# Un_Battery_V2_1.net
KiCad netlist of a schematic drawn in EAGLE
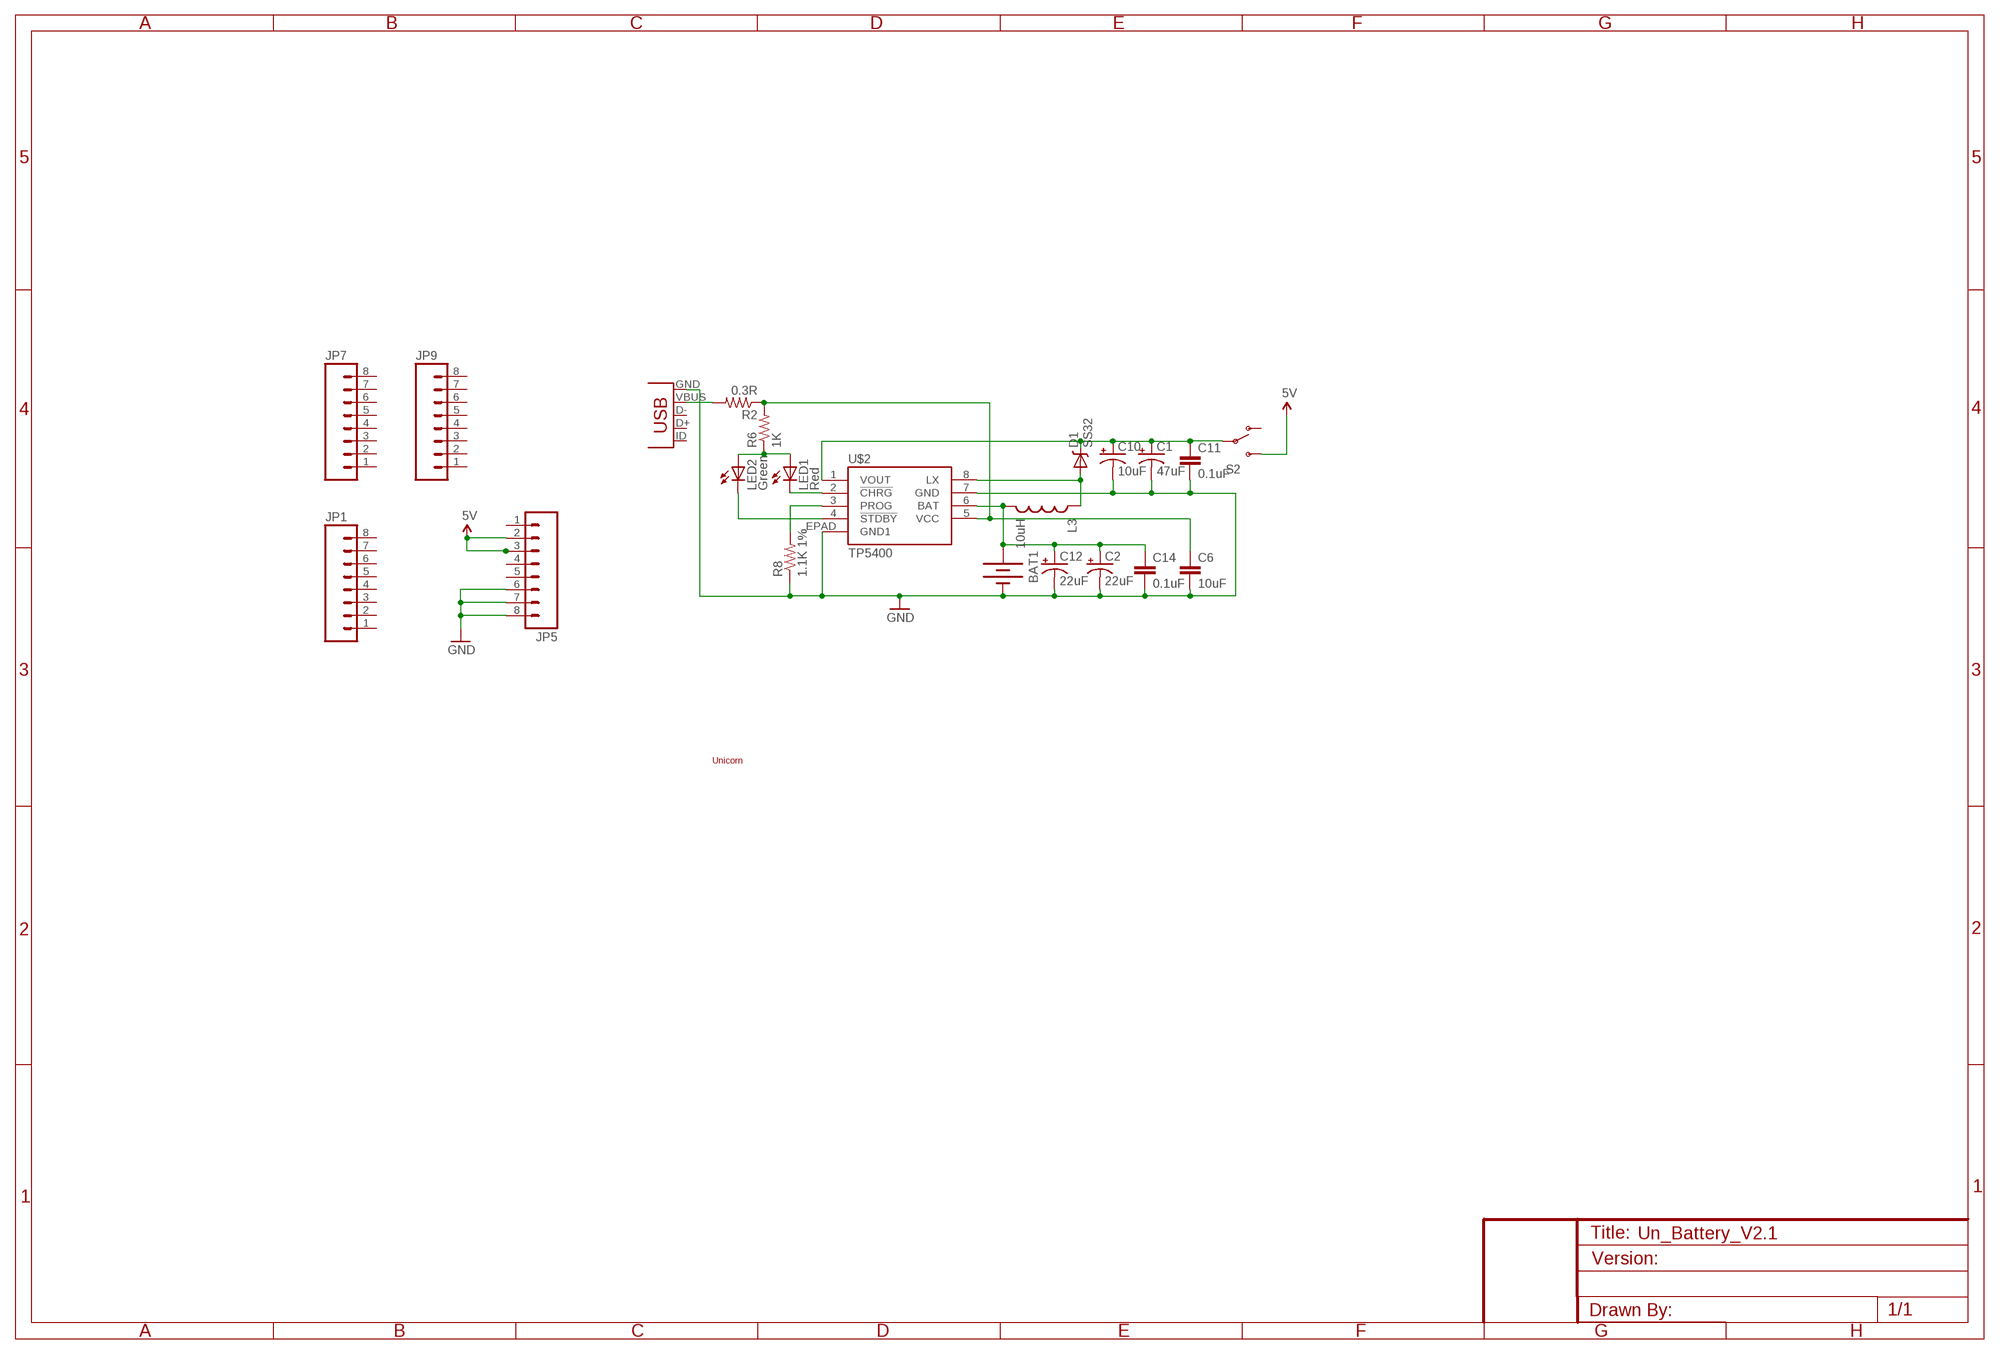
[diagram p0: schematic, sheet 1]

(export (version "E")
  (design (tool "Eeschema 10.0.6"))
  (components
    (comp (ref "BAT1")
      (value "BATTERYLIPO2")
      (footprint "eagle-import:BATTERY-LIPO2")
      (libsource (lib "eagle-import") (part "BATTERYLIPO2"))
    )
    (comp (ref "C1")
      (value "47uF")
      (footprint "eagle-import:EIA3216")
      (libsource (lib "eagle-import") (part "CAP_POL1206"))
    )
    (comp (ref "C2")
      (value "22uF")
      (footprint "eagle-import:EIA3216")
      (libsource (lib "eagle-import") (part "CAP_POL1206"))
    )
    (comp (ref "C6")
      (value "10uF")
      (footprint "eagle-import:1206")
      (libsource (lib "eagle-import") (part "CAP1206"))
    )
    (comp (ref "C10")
      (value "10uF")
      (footprint "eagle-import:EIA3216")
      (libsource (lib "eagle-import") (part "CAP_POL1206"))
    )
    (comp (ref "C11")
      (value "0.1uF")
      (footprint "eagle-import:0603-CAP")
      (libsource (lib "eagle-import") (part "CAP0603-CAP"))
    )
    (comp (ref "C12")
      (value "22uF")
      (footprint "eagle-import:EIA3216")
      (libsource (lib "eagle-import") (part "CAP_POL1206"))
    )
    (comp (ref "C14")
      (value "0.1uF")
      (footprint "eagle-import:0603-CAP")
      (libsource (lib "eagle-import") (part "CAP0603-CAP"))
    )
    (comp (ref "D1")
      (value "SS32")
      (footprint "eagle-import:SMA-DIODE")
      (libsource (lib "eagle-import") (part "DIODE-SCHOTTKY_"))
    )
    (comp (ref "JP1")
      (value "M081X08")
      (footprint "eagle-import:1X08")
      (libsource (lib "eagle-import") (part "M081X08"))
    )
    (comp (ref "JP5")
      (value "M081X08")
      (footprint "eagle-import:1X08")
      (libsource (lib "eagle-import") (part "M081X08"))
    )
    (comp (ref "JP7")
      (value "M081X08")
      (footprint "eagle-import:1X08")
      (libsource (lib "eagle-import") (part "M081X08"))
    )
    (comp (ref "JP9")
      (value "M081X08")
      (footprint "eagle-import:1X08")
      (libsource (lib "eagle-import") (part "M081X08"))
    )
    (comp (ref "L3")
      (value "10uH")
      (footprint "eagle-import:CR32")
      (libsource (lib "eagle-import") (part "INDUCTOR_CR32"))
    )
    (comp (ref "LED1")
      (value "Red")
      (footprint "eagle-import:LED-0603")
      (libsource (lib "eagle-import") (part "LED0603"))
    )
    (comp (ref "LED2")
      (value "Green")
      (footprint "eagle-import:LED-0603")
      (libsource (lib "eagle-import") (part "LED0603"))
    )
    (comp (ref "R2")
      (value "0.3R")
      (footprint "eagle-import:1206")
      (libsource (lib "eagle-import") (part "RESISTOR1206"))
    )
    (comp (ref "R6")
      (value "1K")
      (footprint "eagle-import:0603-RES")
      (libsource (lib "eagle-import") (part "RESISTOR0603-RES"))
    )
    (comp (ref "R8")
      (value "1.1K 1%")
      (footprint "eagle-import:0603-RES")
      (libsource (lib "eagle-import") (part "RESISTOR0603-RES"))
    )
    (comp (ref "S2")
      (value "SWITCH-SPST")
      (footprint "eagle-import:SWITCH-SPDT2")
      (libsource (lib "eagle-import") (part "SWITCH-SPST"))
    )
    (comp (ref "U$2")
      (value "TP5400")
      (footprint "eagle-import:SO08-EPAD")
      (libsource (lib "eagle-import") (part "TP5400"))
    )
    (comp (ref "U$6")
      (value "USB_5-SMD")
      (footprint "eagle-import:USB-MINIB")
      (libsource (lib "eagle-import") (part "USB_5-SMD"))
    )
    (comp (ref "U$7")
      (value "UNICORN_1")
      (footprint "eagle-import:UNICORN_1")
      (libsource (lib "eagle-import") (part "UNICORN_1"))
    )
  )
  (nets
    (net (code "1") (name "5V") (class "Default")
      (node (ref "JP5") (pin "2") (pinfunction "2_2") (pintype "passive"))
      (node (ref "JP5") (pin "3") (pinfunction "3_3") (pintype "passive"))
      (node (ref "S2") (pin "3") (pinfunction "S_3") (pintype "passive"))
    )
    (net (code "2") (name "GND") (class "Default")
      (node (ref "BAT1") (pin "-") (pinfunction "-_-") (pintype "power_in"))
      (node (ref "C1") (pin "C") (pinfunction "-_C") (pintype "passive"))
      (node (ref "C10") (pin "C") (pinfunction "-_C") (pintype "passive"))
      (node (ref "C11") (pin "2") (pinfunction "2_2") (pintype "passive"))
      (node (ref "C12") (pin "C") (pinfunction "-_C") (pintype "passive"))
      (node (ref "C14") (pin "2") (pinfunction "2_2") (pintype "passive"))
      (node (ref "C2") (pin "C") (pinfunction "-_C") (pintype "passive"))
      (node (ref "C6") (pin "2") (pinfunction "2_2") (pintype "passive"))
      (node (ref "JP5") (pin "6") (pinfunction "6_6") (pintype "passive"))
      (node (ref "JP5") (pin "7") (pinfunction "7_7") (pintype "passive"))
      (node (ref "JP5") (pin "8") (pinfunction "8_8") (pintype "passive"))
      (node (ref "R8") (pin "1") (pinfunction "1_1") (pintype "passive"))
      (node (ref "U$2") (pin "7") (pinfunction "GND_7") (pintype "bidirectional"))
      (node (ref "U$2") (pin "EPAD") (pinfunction "GND1_EPAD") (pintype "power_in"))
      (node (ref "U$6") (pin "GND") (pinfunction "GND_GND") (pintype "bidirectional"))
    )
    (net (code "3") (name "Net-(C1-+)") (class "Default")
      (node (ref "C1") (pin "A") (pinfunction "+_A") (pintype "passive"))
      (node (ref "C10") (pin "A") (pinfunction "+_A") (pintype "passive"))
      (node (ref "C11") (pin "1") (pinfunction "1_1") (pintype "passive"))
      (node (ref "D1") (pin "C") (pinfunction "C_C") (pintype "passive"))
      (node (ref "S2") (pin "2") (pinfunction "P_2") (pintype "passive"))
      (node (ref "U$2") (pin "1") (pinfunction "VOUT_1") (pintype "bidirectional"))
    )
    (net (code "4") (name "Net-(C12-+)") (class "Default")
      (node (ref "BAT1") (pin "+") (pinfunction "+_+") (pintype "power_in"))
      (node (ref "C12") (pin "A") (pinfunction "+_A") (pintype "passive"))
      (node (ref "C14") (pin "1") (pinfunction "1_1") (pintype "passive"))
      (node (ref "C2") (pin "A") (pinfunction "+_A") (pintype "passive"))
      (node (ref "L3") (pin "P$2") (pinfunction "2_P$2") (pintype "passive"))
      (node (ref "U$2") (pin "6") (pinfunction "BAT_6") (pintype "bidirectional"))
    )
    (net (code "5") (name "Net-(L3-1)") (class "Default")
      (node (ref "D1") (pin "A") (pinfunction "A_A") (pintype "passive"))
      (node (ref "L3") (pin "P$1") (pinfunction "1_P$1") (pintype "passive"))
      (node (ref "U$2") (pin "8") (pinfunction "LX_8") (pintype "power_in"))
    )
    (net (code "6") (name "Net-(LED1-PadA)") (class "Default")
      (node (ref "LED1") (pin "A") (pinfunction "A_A") (pintype "passive"))
      (node (ref "LED2") (pin "A") (pinfunction "A_A") (pintype "passive"))
      (node (ref "R6") (pin "1") (pinfunction "1_1") (pintype "passive"))
    )
    (net (code "7") (name "Net-(R2-Pad2)") (class "Default")
      (node (ref "R2") (pin "2") (pinfunction "2_2") (pintype "passive"))
      (node (ref "U$6") (pin "VBUS") (pinfunction "VBUS_VBUS") (pintype "bidirectional"))
    )
    (net (code "8") (name "Net-(U$2-PROG)") (class "Default")
      (node (ref "R8") (pin "2") (pinfunction "2_2") (pintype "passive"))
      (node (ref "U$2") (pin "3") (pinfunction "PROG_3") (pintype "bidirectional"))
    )
    (net (code "9") (name "Net-(U$2-VCC)") (class "Default")
      (node (ref "C6") (pin "1") (pinfunction "1_1") (pintype "passive"))
      (node (ref "R2") (pin "1") (pinfunction "1_1") (pintype "passive"))
      (node (ref "R6") (pin "2") (pinfunction "2_2") (pintype "passive"))
      (node (ref "U$2") (pin "5") (pinfunction "VCC_5") (pintype "bidirectional"))
    )
    (net (code "10") (name "Net-(U$2-~{CHRG})") (class "Default")
      (node (ref "LED1") (pin "C") (pinfunction "C_C") (pintype "passive"))
      (node (ref "U$2") (pin "2") (pinfunction "~{CHRG}_2") (pintype "bidirectional"))
    )
    (net (code "11") (name "Net-(U$2-~{STDBY})") (class "Default")
      (node (ref "LED2") (pin "C") (pinfunction "C_C") (pintype "passive"))
      (node (ref "U$2") (pin "4") (pinfunction "~{STDBY}_4") (pintype "power_in"))
    )
    (net (code "12") (name "unconnected-(JP1-Pad1)") (class "Default")
      (node (ref "JP1") (pin "1") (pinfunction "1_1") (pintype "passive"))
    )
    (net (code "13") (name "unconnected-(JP1-Pad2)") (class "Default")
      (node (ref "JP1") (pin "2") (pinfunction "2_2") (pintype "passive"))
    )
    (net (code "14") (name "unconnected-(JP1-Pad3)") (class "Default")
      (node (ref "JP1") (pin "3") (pinfunction "3_3") (pintype "passive"))
    )
    (net (code "15") (name "unconnected-(JP1-Pad4)") (class "Default")
      (node (ref "JP1") (pin "4") (pinfunction "4_4") (pintype "passive"))
    )
    (net (code "16") (name "unconnected-(JP1-Pad5)") (class "Default")
      (node (ref "JP1") (pin "5") (pinfunction "5_5") (pintype "passive"))
    )
    (net (code "17") (name "unconnected-(JP1-Pad6)") (class "Default")
      (node (ref "JP1") (pin "6") (pinfunction "6_6") (pintype "passive"))
    )
    (net (code "18") (name "unconnected-(JP1-Pad7)") (class "Default")
      (node (ref "JP1") (pin "7") (pinfunction "7_7") (pintype "passive"))
    )
    (net (code "19") (name "unconnected-(JP1-Pad8)") (class "Default")
      (node (ref "JP1") (pin "8") (pinfunction "8_8") (pintype "passive"))
    )
    (net (code "20") (name "unconnected-(JP5-Pad1)") (class "Default")
      (node (ref "JP5") (pin "1") (pinfunction "1_1") (pintype "passive"))
    )
    (net (code "21") (name "unconnected-(JP5-Pad4)") (class "Default")
      (node (ref "JP5") (pin "4") (pinfunction "4_4") (pintype "passive"))
    )
    (net (code "22") (name "unconnected-(JP5-Pad5)") (class "Default")
      (node (ref "JP5") (pin "5") (pinfunction "5_5") (pintype "passive"))
    )
    (net (code "23") (name "unconnected-(JP7-Pad1)") (class "Default")
      (node (ref "JP7") (pin "1") (pinfunction "1_1") (pintype "passive"))
    )
    (net (code "24") (name "unconnected-(JP7-Pad2)") (class "Default")
      (node (ref "JP7") (pin "2") (pinfunction "2_2") (pintype "passive"))
    )
    (net (code "25") (name "unconnected-(JP7-Pad3)") (class "Default")
      (node (ref "JP7") (pin "3") (pinfunction "3_3") (pintype "passive"))
    )
    (net (code "26") (name "unconnected-(JP7-Pad4)") (class "Default")
      (node (ref "JP7") (pin "4") (pinfunction "4_4") (pintype "passive"))
    )
    (net (code "27") (name "unconnected-(JP7-Pad5)") (class "Default")
      (node (ref "JP7") (pin "5") (pinfunction "5_5") (pintype "passive"))
    )
    (net (code "28") (name "unconnected-(JP7-Pad6)") (class "Default")
      (node (ref "JP7") (pin "6") (pinfunction "6_6") (pintype "passive"))
    )
    (net (code "29") (name "unconnected-(JP7-Pad7)") (class "Default")
      (node (ref "JP7") (pin "7") (pinfunction "7_7") (pintype "passive"))
    )
    (net (code "30") (name "unconnected-(JP7-Pad8)") (class "Default")
      (node (ref "JP7") (pin "8") (pinfunction "8_8") (pintype "passive"))
    )
    (net (code "31") (name "unconnected-(JP9-Pad1)") (class "Default")
      (node (ref "JP9") (pin "1") (pinfunction "1_1") (pintype "passive"))
    )
    (net (code "32") (name "unconnected-(JP9-Pad2)") (class "Default")
      (node (ref "JP9") (pin "2") (pinfunction "2_2") (pintype "passive"))
    )
    (net (code "33") (name "unconnected-(JP9-Pad3)") (class "Default")
      (node (ref "JP9") (pin "3") (pinfunction "3_3") (pintype "passive"))
    )
    (net (code "34") (name "unconnected-(JP9-Pad4)") (class "Default")
      (node (ref "JP9") (pin "4") (pinfunction "4_4") (pintype "passive"))
    )
    (net (code "35") (name "unconnected-(JP9-Pad5)") (class "Default")
      (node (ref "JP9") (pin "5") (pinfunction "5_5") (pintype "passive"))
    )
    (net (code "36") (name "unconnected-(JP9-Pad6)") (class "Default")
      (node (ref "JP9") (pin "6") (pinfunction "6_6") (pintype "passive"))
    )
    (net (code "37") (name "unconnected-(JP9-Pad7)") (class "Default")
      (node (ref "JP9") (pin "7") (pinfunction "7_7") (pintype "passive"))
    )
    (net (code "38") (name "unconnected-(JP9-Pad8)") (class "Default")
      (node (ref "JP9") (pin "8") (pinfunction "8_8") (pintype "passive"))
    )
    (net (code "39") (name "unconnected-(S2-O-Pad1)") (class "Default")
      (node (ref "S2") (pin "1") (pinfunction "O_1") (pintype "passive"))
    )
    (net (code "40") (name "unconnected-(U$6-PadD+)") (class "Default")
      (node (ref "U$6") (pin "D+") (pinfunction "D+_D+") (pintype "bidirectional"))
    )
    (net (code "41") (name "unconnected-(U$6-PadD-)") (class "Default")
      (node (ref "U$6") (pin "D-") (pinfunction "D-_D-") (pintype "bidirectional"))
    )
    (net (code "42") (name "unconnected-(U$6-USBID-PadID)") (class "Default")
      (node (ref "U$6") (pin "ID") (pinfunction "USBID_ID") (pintype "bidirectional"))
    )
  )
)
